# Power_Supply_3.net
KiCad netlist of a schematic drawn in Altium Designer
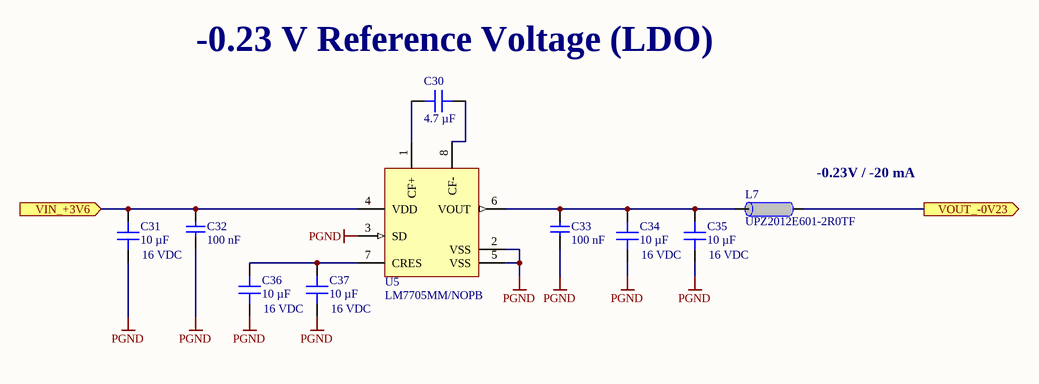
[diagram p0: Power_Supply_3.SchDoc]

(export (version "E")
  (design (tool "Eeschema 10.0.6"))
  (components
    (comp (ref "C30")
      (value "4.7 µF")
      (footprint "C_0805")
      (description "25V 4.7uF X5R ±10% 0805  Multilayer Ceramic Capacitors MLCC - SMD/SMT ROHS")
      (fields
        (field (name "MANUFACTURER PART NUMBER") "CL21A475KAQNNNE")
        (field (name "MANUFACTURER") "Samsung Electro-Mechanics")
        (field (name "CREATED FROM") "AGeiger")
      )
      (libsource (lib "user") (part "Capacitor"))
    )
    (comp (ref "C31")
      (value "10 µF")
      (footprint "C_0603_TE")
      (description "Capacitor 0603, 16 VDC, 10 µF, X5R")
      (fields
        (field (name "MANUFACTURER PART NUMBER") "CL10A106MO8NQNC")
        (field (name "MANUFACTURER") "Samsung Electro-Mechanics")
        (field (name "VOLTAGE RATING") "16 VDC")
        (field (name "CREATED FROM") "AGeiger")
      )
      (libsource (lib "user") (part "Capacitor"))
    )
    (comp (ref "C32")
      (value "100 nF")
      (footprint "C_0603_TE")
      (description "Generic capacitor")
      (fields
        (field (name "MANUFACTURER PART NUMBER") "UZgen_C_0603_100nF_50V_X7R")
        (field (name "MANUFACTURER") "UZgen")
        (field (name "CREATED FROM") "AGeiger")
      )
      (libsource (lib "user") (part "CAP-NP"))
    )
    (comp (ref "C33")
      (value "100 nF")
      (footprint "C_0603_TE")
      (description "Generic capacitor")
      (fields
        (field (name "MANUFACTURER PART NUMBER") "UZgen_C_0603_100nF_50V_X7R")
        (field (name "MANUFACTURER") "UZgen")
        (field (name "CREATED FROM") "AGeiger")
      )
      (libsource (lib "user") (part "CAP-NP"))
    )
    (comp (ref "C34")
      (value "10 µF")
      (footprint "C_0603_TE")
      (description "Capacitor 0603, 16 VDC, 10 µF, X5R")
      (fields
        (field (name "MANUFACTURER PART NUMBER") "CL10A106MO8NQNC")
        (field (name "MANUFACTURER") "Samsung Electro-Mechanics")
        (field (name "VOLTAGE RATING") "16 VDC")
        (field (name "CREATED FROM") "AGeiger")
      )
      (libsource (lib "user") (part "Capacitor"))
    )
    (comp (ref "C35")
      (value "10 µF")
      (footprint "C_0603_TE")
      (description "Capacitor 0603, 16 VDC, 10 µF, X5R")
      (fields
        (field (name "MANUFACTURER PART NUMBER") "CL10A106MO8NQNC")
        (field (name "MANUFACTURER") "Samsung Electro-Mechanics")
        (field (name "VOLTAGE RATING") "16 VDC")
        (field (name "CREATED FROM") "AGeiger")
      )
      (libsource (lib "user") (part "Capacitor"))
    )
    (comp (ref "C36")
      (value "10 µF")
      (footprint "C_0603_TE")
      (description "Capacitor 0603, 16 VDC, 10 µF, X5R")
      (fields
        (field (name "MANUFACTURER PART NUMBER") "CL10A106MO8NQNC")
        (field (name "MANUFACTURER") "Samsung Electro-Mechanics")
        (field (name "VOLTAGE RATING") "16 VDC")
        (field (name "CREATED FROM") "AGeiger")
      )
      (libsource (lib "user") (part "Capacitor"))
    )
    (comp (ref "C37")
      (value "10 µF")
      (footprint "C_0603_TE")
      (description "Capacitor 0603, 16 VDC, 10 µF, X5R")
      (fields
        (field (name "MANUFACTURER PART NUMBER") "CL10A106MO8NQNC")
        (field (name "MANUFACTURER") "Samsung Electro-Mechanics")
        (field (name "VOLTAGE RATING") "16 VDC")
        (field (name "CREATED FROM") "AGeiger")
      )
      (libsource (lib "user") (part "Capacitor"))
    )
    (comp (ref "L7")
      (value "UPZ2012E601-2R0TF")
      (footprint "INDC2012X92N_V")
      (description "2A 1 90mΩ 600Ω@100MHz ±25% 0805  Ferrite Beads ROHS")
      (fields
        (field (name "MANUFACTURER") "Sunlord")
        (field (name "LCSC PART NUMBER") "C98308")
        (field (name "CREATED FROM") "AGeiger")
      )
      (libsource (lib "user") (part "Ferrite_Bead"))
    )
    (comp (ref "U5")
      (value "LM7705MM/NOPB")
      (footprint "MSOP-8_DGK0008A_L")
      (description "Low-Noise Negative Bias Generator")
      (fields
        (field (name "MF") "Texas Instruments")
        (field (name "LCSC PART NUMBER") "C129980")
        (field (name "CREATED FROM") "AGeiger")
      )
      (libsource (lib "user") (part "LM7705"))
    )
  )
  (nets
    (net (code "1") (name "/VIN_+3V6") (class "Default")
      (node (ref "C31") (pin "2") (pinfunction "2_2") (pintype "passive"))
      (node (ref "C32") (pin "2") (pinfunction "2_2") (pintype "passive"))
      (node (ref "U5") (pin "4") (pinfunction "VDD_4") (pintype "power_in"))
    )
    (net (code "2") (name "/VOUT_-0V23") (class "Default")
      (node (ref "L7") (pin "1") (pinfunction "1_1") (pintype "passive"))
    )
    (net (code "3") (name "Net-(U5-CF+)") (class "Default")
      (node (ref "C30") (pin "1") (pinfunction "1_1") (pintype "passive"))
      (node (ref "U5") (pin "1") (pinfunction "CF+_1") (pintype "passive"))
    )
    (net (code "4") (name "Net-(U5-CF-)") (class "Default")
      (node (ref "C30") (pin "2") (pinfunction "2_2") (pintype "passive"))
      (node (ref "U5") (pin "8") (pinfunction "CF-_8") (pintype "passive"))
    )
    (net (code "5") (name "Net-(U5-CRES)") (class "Default")
      (node (ref "C36") (pin "2") (pinfunction "2_2") (pintype "passive"))
      (node (ref "C37") (pin "2") (pinfunction "2_2") (pintype "passive"))
      (node (ref "U5") (pin "7") (pinfunction "CRES_7") (pintype "passive"))
    )
    (net (code "6") (name "Net-(U5-VOUT)") (class "Default")
      (node (ref "C33") (pin "2") (pinfunction "2_2") (pintype "passive"))
      (node (ref "C34") (pin "2") (pinfunction "2_2") (pintype "passive"))
      (node (ref "C35") (pin "2") (pinfunction "2_2") (pintype "passive"))
      (node (ref "L7") (pin "2") (pinfunction "2_2") (pintype "passive"))
      (node (ref "U5") (pin "6") (pinfunction "VOUT_6") (pintype "output"))
    )
    (net (code "7") (name "PGND") (class "Default")
      (node (ref "C31") (pin "1") (pinfunction "1_1") (pintype "passive"))
      (node (ref "C32") (pin "1") (pinfunction "1_1") (pintype "passive"))
      (node (ref "C33") (pin "1") (pinfunction "1_1") (pintype "passive"))
      (node (ref "C34") (pin "1") (pinfunction "1_1") (pintype "passive"))
      (node (ref "C35") (pin "1") (pinfunction "1_1") (pintype "passive"))
      (node (ref "C36") (pin "1") (pinfunction "1_1") (pintype "passive"))
      (node (ref "C37") (pin "1") (pinfunction "1_1") (pintype "passive"))
      (node (ref "U5") (pin "2") (pinfunction "VSS_2") (pintype "power_in"))
      (node (ref "U5") (pin "3") (pinfunction "SD_3") (pintype "input"))
      (node (ref "U5") (pin "5") (pinfunction "VSS_5") (pintype "power_in"))
    )
  )
)
